# loggerV3_0.net
KiCad netlist of a schematic drawn in EAGLE
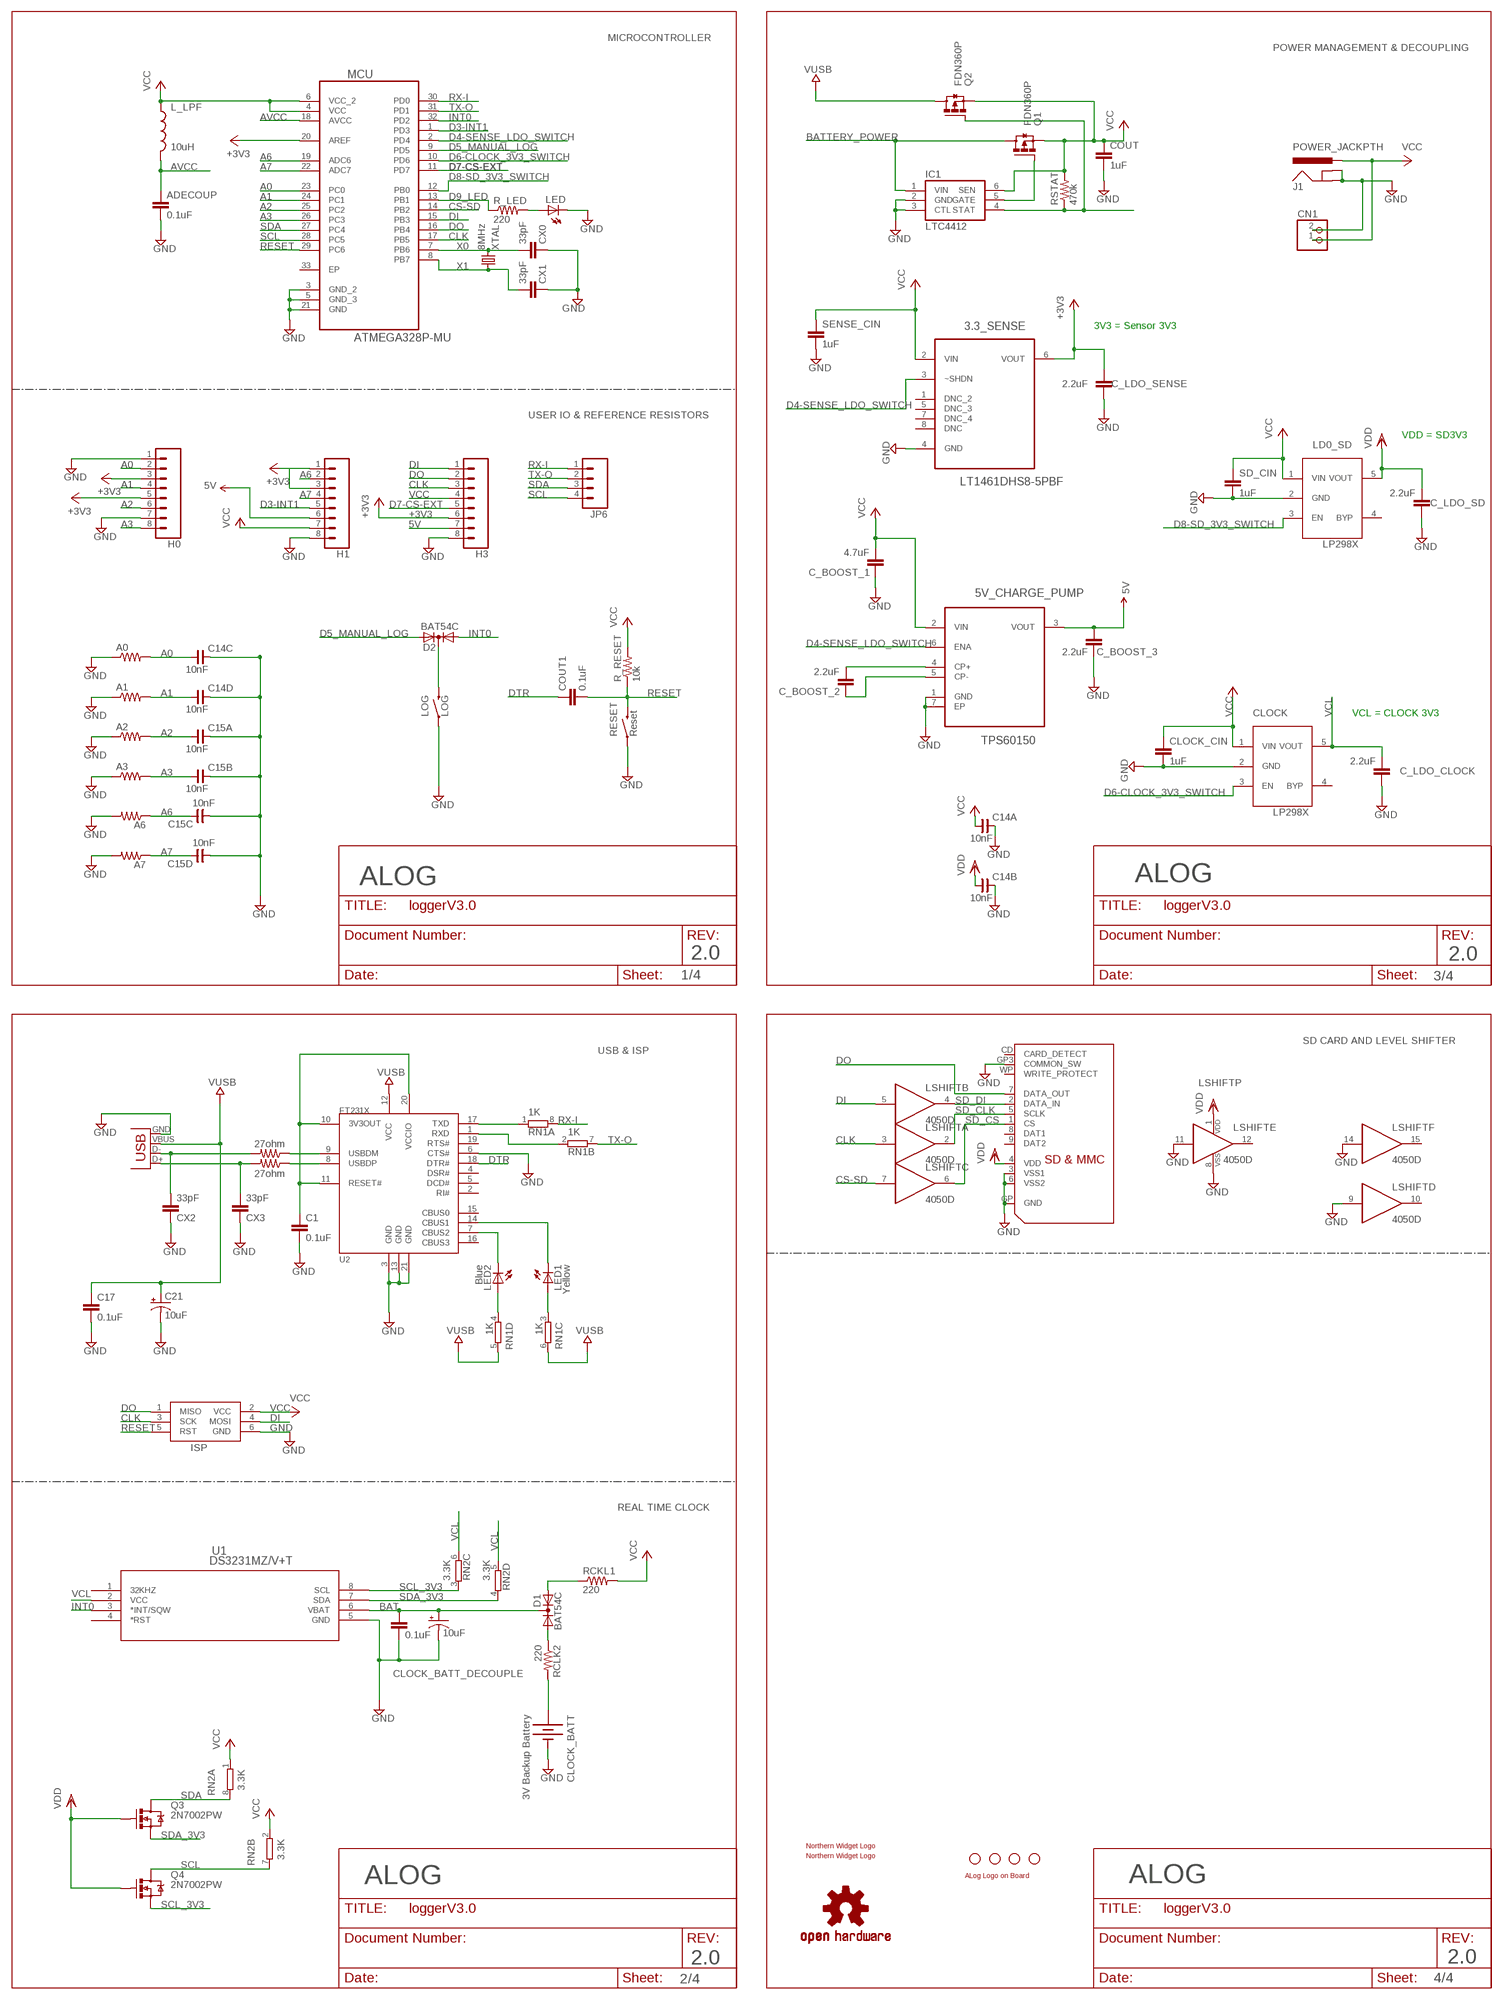
[diagram p0: schematic, sheet 1]

(export (version "E")
  (design (tool "Eeschema 10.0.6"))
  (components
    (comp (ref "3.3_SENSE")
      (value "LT1461DHS8-5PBF")
      (footprint "eagle-import:SOIC127P600X175-8N")
      (fields (field (name "MPN") "LT1461DHS8-5#PBF"))
      (libsource (lib "eagle-import") (part "LT1461DHS8-5PBF"))
    )
    (comp (ref "5V_CHARGE_PUMP")
      (value "TPS60150")
      (footprint "eagle-import:SON65P200X200X80-7N")
      (fields (field (name "MPN") "TPS60150DRVR"))
      (libsource (lib "eagle-import") (part "TPS60150DRVR"))
    )
    (comp (ref "A0")
      (value "R-US_0207/10")
      (footprint "eagle-import:0207_10")
      (libsource (lib "eagle-import") (part "resistor_R-US_0207/10"))
    )
    (comp (ref "A1")
      (value "R-US_0207/10")
      (footprint "eagle-import:0207_10")
      (libsource (lib "eagle-import") (part "resistor_R-US_0207/10"))
    )
    (comp (ref "A2")
      (value "R-US_0207/10")
      (footprint "eagle-import:0207_10")
      (libsource (lib "eagle-import") (part "resistor_R-US_0207/10"))
    )
    (comp (ref "A3")
      (value "R-US_0207/10")
      (footprint "eagle-import:0207_10")
      (libsource (lib "eagle-import") (part "resistor_R-US_0207/10"))
    )
    (comp (ref "A6")
      (value "R-US_0207/10")
      (footprint "eagle-import:0207_10")
      (libsource (lib "eagle-import") (part "resistor_R-US_0207/10"))
    )
    (comp (ref "A7")
      (value "R-US_0207/10")
      (footprint "eagle-import:0207_10")
      (libsource (lib "eagle-import") (part "resistor_R-US_0207/10"))
    )
    (comp (ref "ADECOUP")
      (value "0.1uF")
      (footprint "eagle-import:C0603")
      (libsource (lib "eagle-import") (part "resistor_C-EUC0603"))
    )
    (comp (ref "C1")
      (value "0.1uF")
      (footprint "eagle-import:C0603")
      (libsource (lib "eagle-import") (part "resistor_C-EUC0603"))
    )
    (comp (ref "C14")
      (value "10nF")
      (footprint "eagle-import:CECJ-1206")
      (libsource (lib "eagle-import") (part "CCA_ECJ-1206"))
    )
    (comp (ref "C15")
      (value "10nF")
      (footprint "eagle-import:CECJ-1206")
      (libsource (lib "eagle-import") (part "CCA_ECJ-1206"))
    )
    (comp (ref "C17")
      (value "0.1uF")
      (footprint "eagle-import:C0603")
      (libsource (lib "eagle-import") (part "resistor_C-EUC0603"))
    )
    (comp (ref "C21")
      (value "10uF")
      (footprint "eagle-import:EIA3216")
      (libsource (lib "eagle-import") (part "CAP_POL1206"))
    )
    (comp (ref "CLOCK")
      (value "LP2985")
      (footprint "eagle-import:SOT23-5L")
      (libsource (lib "eagle-import") (part "LP298XS"))
    )
    (comp (ref "CLOCK_BATT")
      (value "3V Backup Battery")
      (footprint "eagle-import:BATTCON_12MM_PTH")
      (libsource (lib "eagle-import") (part "BATTERY12PTH"))
    )
    (comp (ref "CLOCK_BATT_DECOUP")
      (value "0.1uF")
      (footprint "eagle-import:C0603")
      (libsource (lib "eagle-import") (part "C-EUC0603"))
    )
    (comp (ref "CLOCK_BATT_DECOUPLE")
      (value "10uF")
      (footprint "eagle-import:EIA3216")
      (libsource (lib "eagle-import") (part "CAP_POL1206"))
    )
    (comp (ref "CLOCK_CIN")
      (value "1uF")
      (footprint "eagle-import:C0603")
      (libsource (lib "eagle-import") (part "C-EUC0603"))
    )
    (comp (ref "CN1")
      (value "JST_2PIN-THM")
      (footprint "eagle-import:JST-PH-2-THM")
      (libsource (lib "eagle-import") (part "JST_2PIN-THM"))
    )
    (comp (ref "COUT")
      (value "1uF")
      (footprint "eagle-import:C0603")
      (libsource (lib "eagle-import") (part "C-EUC0603"))
    )
    (comp (ref "COUT1")
      (value "0.1uF")
      (footprint "eagle-import:C0603")
      (libsource (lib "eagle-import") (part "C-EUC0603"))
    )
    (comp (ref "CX0")
      (value "33pF")
      (footprint "eagle-import:C0603")
      (libsource (lib "eagle-import") (part "resistor_C-EUC0603"))
    )
    (comp (ref "CX1")
      (value "33pF")
      (footprint "eagle-import:C0603")
      (libsource (lib "eagle-import") (part "resistor_C-EUC0603"))
    )
    (comp (ref "CX2")
      (value "33pF")
      (footprint "eagle-import:C0603")
      (libsource (lib "eagle-import") (part "resistor_C-EUC0603"))
    )
    (comp (ref "CX3")
      (value "33pF")
      (footprint "eagle-import:C0603")
      (libsource (lib "eagle-import") (part "resistor_C-EUC0603"))
    )
    (comp (ref "C_BOOST_1")
      (value "4.7uF")
      (footprint "eagle-import:C0603")
      (libsource (lib "eagle-import") (part "resistor_C-EUC0603"))
    )
    (comp (ref "C_BOOST_2")
      (value "2.2uF")
      (footprint "eagle-import:C0603")
      (libsource (lib "eagle-import") (part "resistor_C-EUC0603"))
    )
    (comp (ref "C_BOOST_3")
      (value "2.2uF")
      (footprint "eagle-import:C0603")
      (libsource (lib "eagle-import") (part "resistor_C-EUC0603"))
    )
    (comp (ref "C_LDO_CLOCK")
      (value "2.2uF")
      (footprint "eagle-import:C0603")
      (libsource (lib "eagle-import") (part "resistor_C-EUC0603"))
    )
    (comp (ref "C_LDO_SD")
      (value "2.2uF")
      (footprint "eagle-import:C0603")
      (libsource (lib "eagle-import") (part "resistor_C-EUC0603"))
    )
    (comp (ref "C_LDO_SENSE")
      (value "2.2uF")
      (footprint "eagle-import:C0603")
      (libsource (lib "eagle-import") (part "resistor_C-EUC0603"))
    )
    (comp (ref "D+")
      (value "27ohm")
      (footprint "eagle-import:R0603")
      (libsource (lib "eagle-import") (part "R-US_R0603"))
    )
    (comp (ref "D-")
      (value "27ohm")
      (footprint "eagle-import:R0603")
      (libsource (lib "eagle-import") (part "R-US_R0603"))
    )
    (comp (ref "D1")
      (value "BAT54C")
      (footprint "eagle-import:SOT23C")
      (libsource (lib "eagle-import") (part "DIODE_AC-CA_"))
    )
    (comp (ref "D2")
      (value "BAT54C")
      (footprint "eagle-import:SOT23C")
      (libsource (lib "eagle-import") (part "DIODE_AC-CA_"))
    )
    (comp (ref "H0")
      (value "M083.5MM-8")
      (footprint "eagle-import:SCREWTERMINAL-3.5MM-8")
      (libsource (lib "eagle-import") (part "M083.5MM-8"))
    )
    (comp (ref "H1")
      (value "M083.5MM-8")
      (footprint "eagle-import:SCREWTERMINAL-3.5MM-8")
      (libsource (lib "eagle-import") (part "M083.5MM-8"))
    )
    (comp (ref "H3")
      (value "M083.5MM-8")
      (footprint "eagle-import:SCREWTERMINAL-3.5MM-8")
      (libsource (lib "eagle-import") (part "M083.5MM-8"))
    )
    (comp (ref "IC1")
      (value "LTC4412")
      (footprint "eagle-import:TSOT23-6")
      (libsource (lib "eagle-import") (part "LTC4412S6E"))
    )
    (comp (ref "ISP")
      (value "AVRISP-6")
      (footprint "eagle-import:AVRISP")
      (libsource (lib "eagle-import") (part "AVRISP-6"))
    )
    (comp (ref "J1")
      (value "POWER_JACKPTH")
      (footprint "eagle-import:POWER_JACK_PTH")
      (libsource (lib "eagle-import") (part "POWER_JACKPTH"))
    )
    (comp (ref "JP1")
      (value "STAND-OFF")
      (footprint "eagle-import:STAND-OFF")
      (libsource (lib "eagle-import") (part "STAND-OFF"))
    )
    (comp (ref "JP2")
      (value "STAND-OFF")
      (footprint "eagle-import:STAND-OFF")
      (libsource (lib "eagle-import") (part "STAND-OFF"))
    )
    (comp (ref "JP3")
      (value "STAND-OFF")
      (footprint "eagle-import:STAND-OFF")
      (libsource (lib "eagle-import") (part "STAND-OFF"))
    )
    (comp (ref "JP4")
      (value "STAND-OFF")
      (footprint "eagle-import:STAND-OFF")
      (libsource (lib "eagle-import") (part "STAND-OFF"))
    )
    (comp (ref "JP5")
      (value "USB-B")
      (footprint "eagle-import:USB-B-PTH")
      (libsource (lib "eagle-import") (part "USBPTH"))
    )
    (comp (ref "JP6")
      (value "M04SCREW")
      (footprint "eagle-import:SCREWTERMINAL-3.5MM-4")
      (libsource (lib "eagle-import") (part "M04SCREW"))
    )
    (comp (ref "LD0_SD")
      (value "LP2985")
      (footprint "eagle-import:SOT23-5L")
      (libsource (lib "eagle-import") (part "LP298XS"))
    )
    (comp (ref "LED")
      (value "LED3MM")
      (footprint "eagle-import:LED3MM")
      (libsource (lib "eagle-import") (part "LED3MM"))
    )
    (comp (ref "LED1")
      (value "Yellow")
      (footprint "eagle-import:LED-0603")
      (libsource (lib "eagle-import") (part "SparkFun-LED_LED0603"))
    )
    (comp (ref "LED2")
      (value "Blue")
      (footprint "eagle-import:LED-0603")
      (libsource (lib "eagle-import") (part "SparkFun-LED_LED0603"))
    )
    (comp (ref "LOG")
      (value "LOG")
      (footprint "eagle-import:TACTILE-PTH")
      (libsource (lib "eagle-import") (part "SWITCH-MOMENTARY-2PTH"))
    )
    (comp (ref "LOGO1")
      (value "OSHW-LOGOM")
      (footprint "eagle-import:OSHW-LOGO-M")
      (libsource (lib "eagle-import") (part "OSHW-LOGOM"))
    )
    (comp (ref "LSHIFT")
      (value "4050D")
      (footprint "eagle-import:SO16")
      (libsource (lib "eagle-import") (part "4050D"))
    )
    (comp (ref "L_LPF")
      (value "10uH")
      (footprint "eagle-import:0805")
      (libsource (lib "eagle-import") (part "INDUCTOR0805"))
    )
    (comp (ref "MCU")
      (value "ATMEGA328P-MU")
      (footprint "eagle-import:QFN50P500X500X100-33N")
      (libsource (lib "eagle-import") (part "ATMEGA328P-MU"))
    )
    (comp (ref "Q1")
      (value "FDN360P")
      (footprint "eagle-import:SUPER-SOT3")
      (libsource (lib "eagle-import") (part "FDN360P"))
    )
    (comp (ref "Q2")
      (value "FDN360P")
      (footprint "eagle-import:SUPER-SOT3")
      (libsource (lib "eagle-import") (part "FDN360P"))
    )
    (comp (ref "Q3")
      (value "2N7002PW")
      (footprint "eagle-import:SOT323")
      (libsource (lib "eagle-import") (part "MOSFET-NCHANNELSOT323"))
    )
    (comp (ref "Q4")
      (value "2N7002PW")
      (footprint "eagle-import:SOT323")
      (libsource (lib "eagle-import") (part "MOSFET-NCHANNELSOT323"))
    )
    (comp (ref "RCKL1")
      (value "220")
      (footprint "eagle-import:R0603")
      (libsource (lib "eagle-import") (part "R-US_R0603"))
    )
    (comp (ref "RCLK2")
      (value "220")
      (footprint "eagle-import:R0603")
      (libsource (lib "eagle-import") (part "R-US_R0603"))
    )
    (comp (ref "RESET")
      (value "Reset")
      (footprint "eagle-import:TACTILE-PTH")
      (libsource (lib "eagle-import") (part "SWITCH-MOMENTARY-2PTH"))
    )
    (comp (ref "RN1")
      (value "1K")
      (footprint "eagle-import:0603-ARC")
      (libsource (lib "eagle-import") (part "4R-N0603-ARC"))
    )
    (comp (ref "RN2")
      (value "3.3K")
      (footprint "eagle-import:0603-ARC")
      (libsource (lib "eagle-import") (part "4R-N0603-ARC"))
    )
    (comp (ref "RSTAT")
      (value "470k")
      (footprint "eagle-import:R0603")
      (libsource (lib "eagle-import") (part "R-US_R0603"))
    )
    (comp (ref "R_LED")
      (value "220")
      (footprint "eagle-import:R0603")
      (libsource (lib "eagle-import") (part "resistor_R-US_R0603"))
    )
    (comp (ref "R_RESET")
      (value "10k")
      (footprint "eagle-import:R0603")
      (libsource (lib "eagle-import") (part "R-US_R0603"))
    )
    (comp (ref "SD")
      (value "SDMMC06132")
      (footprint "eagle-import:06132")
      (libsource (lib "eagle-import") (part "SDMMC06132"))
    )
    (comp (ref "SD_CIN")
      (value "1uF")
      (footprint "eagle-import:C0603")
      (libsource (lib "eagle-import") (part "C-EUC0603"))
    )
    (comp (ref "SENSE_CIN")
      (value "1uF")
      (footprint "eagle-import:C0603")
      (libsource (lib "eagle-import") (part "C-EUC0603"))
    )
    (comp (ref "U$1")
      (value "NWLOGO")
      (footprint "eagle-import:NWLOGO")
      (libsource (lib "eagle-import") (part "NWLOGO"))
    )
    (comp (ref "U$2")
      (value "ALOG_LOGO_V1_5.5MM")
      (footprint "eagle-import:ALOG_LOGO_V1_SMALL")
      (libsource (lib "eagle-import") (part "ALOG_LOGO_V1_5.5MM"))
    )
    (comp (ref "U$3")
      (value "NWLOGO_MED")
      (footprint "eagle-import:NWLOGO_MED")
      (libsource (lib "eagle-import") (part "NWLOGO_MED"))
    )
    (comp (ref "U1")
      (value "DS3231MZ/V+T")
      (footprint "eagle-import:21-0041B_8")
      (libsource (lib "eagle-import") (part "DS3231MZ/V+T"))
    )
    (comp (ref "U2")
      (value "FT231X-Q")
      (footprint "eagle-import:QFN20")
      (libsource (lib "eagle-import") (part "FT231X-Q"))
    )
    (comp (ref "XTAL")
      (value "8MHz")
      (footprint "eagle-import:HC49U-V")
      (libsource (lib "eagle-import") (part "CRYSTALHC49UV"))
    )
  )
  (nets
    (net (code "1") (name "+3V3") (class "Default")
      (node (ref "3.3_SENSE") (pin "6") (pinfunction "VOUT_6") (pintype "output"))
      (node (ref "C_LDO_SENSE") (pin "2") (pinfunction "2_2") (pintype "passive"))
      (node (ref "H0") (pin "3") (pinfunction "3_3") (pintype "passive"))
      (node (ref "H0") (pin "5") (pinfunction "5_5") (pintype "passive"))
      (node (ref "H1") (pin "1") (pinfunction "1_1") (pintype "passive"))
      (node (ref "H1") (pin "3") (pinfunction "3_3") (pintype "passive"))
      (node (ref "H3") (pin "6") (pinfunction "6_6") (pintype "passive"))
      (node (ref "MCU") (pin "20") (pinfunction "AREF_20") (pintype "input"))
    )
    (net (code "2") (name "/A0") (class "Default")
      (node (ref "A0") (pin "2") (pinfunction "2_2") (pintype "passive"))
      (node (ref "C14") (pin "C1") (pinfunction "1_C1") (pintype "passive"))
      (node (ref "H0") (pin "2") (pinfunction "2_2") (pintype "passive"))
      (node (ref "MCU") (pin "23") (pinfunction "PC0_23") (pintype "bidirectional"))
    )
    (net (code "3") (name "/A1") (class "Default")
      (node (ref "A1") (pin "2") (pinfunction "2_2") (pintype "passive"))
      (node (ref "C14") (pin "D1") (pinfunction "1_D1") (pintype "passive"))
      (node (ref "H0") (pin "4") (pinfunction "4_4") (pintype "passive"))
      (node (ref "MCU") (pin "24") (pinfunction "PC1_24") (pintype "bidirectional"))
    )
    (net (code "4") (name "/A2") (class "Default")
      (node (ref "A2") (pin "2") (pinfunction "2_2") (pintype "passive"))
      (node (ref "C15") (pin "A1") (pinfunction "1_A1") (pintype "passive"))
      (node (ref "H0") (pin "6") (pinfunction "6_6") (pintype "passive"))
      (node (ref "MCU") (pin "25") (pinfunction "PC2_25") (pintype "bidirectional"))
    )
    (net (code "5") (name "/A3") (class "Default")
      (node (ref "A3") (pin "2") (pinfunction "2_2") (pintype "passive"))
      (node (ref "C15") (pin "B1") (pinfunction "1_B1") (pintype "passive"))
      (node (ref "H0") (pin "8") (pinfunction "8_8") (pintype "passive"))
      (node (ref "MCU") (pin "26") (pinfunction "PC3_26") (pintype "bidirectional"))
    )
    (net (code "6") (name "/A6") (class "Default")
      (node (ref "A6") (pin "1") (pinfunction "1_1") (pintype "passive"))
      (node (ref "C15") (pin "C2") (pinfunction "2_C2") (pintype "passive"))
      (node (ref "H1") (pin "2") (pinfunction "2_2") (pintype "passive"))
      (node (ref "MCU") (pin "19") (pinfunction "ADC6_19") (pintype "input"))
    )
    (net (code "7") (name "/A7") (class "Default")
      (node (ref "A7") (pin "1") (pinfunction "1_1") (pintype "passive"))
      (node (ref "C15") (pin "D2") (pinfunction "2_D2") (pintype "passive"))
      (node (ref "H1") (pin "4") (pinfunction "4_4") (pintype "passive"))
      (node (ref "MCU") (pin "22") (pinfunction "ADC7_22") (pintype "input"))
    )
    (net (code "8") (name "/AVCC") (class "Default")
      (node (ref "ADECOUP") (pin "1") (pinfunction "1_1") (pintype "passive"))
      (node (ref "L_LPF") (pin "2") (pinfunction "2_2") (pintype "passive"))
      (node (ref "MCU") (pin "18") (pinfunction "AVCC_18") (pintype "power_in"))
    )
    (net (code "9") (name "/BAT") (class "Default")
      (node (ref "CLOCK_BATT_DECOUP") (pin "1") (pinfunction "1_1") (pintype "passive"))
      (node (ref "CLOCK_BATT_DECOUPLE") (pin "A") (pinfunction "+_A") (pintype "passive"))
      (node (ref "D1") (pin "3") (pinfunction "K_3") (pintype "passive"))
      (node (ref "U1") (pin "6") (pinfunction "VBAT_6") (pintype "power_in"))
    )
    (net (code "10") (name "/BATTERY_POWER") (class "Default")
      (node (ref "IC1") (pin "1") (pinfunction "VIN_1") (pintype "input"))
      (node (ref "Q1") (pin "3") (pinfunction "D_3") (pintype "passive"))
    )
    (net (code "11") (name "/CLK") (class "Default")
      (node (ref "H3") (pin "3") (pinfunction "3_3") (pintype "passive"))
      (node (ref "ISP") (pin "3") (pinfunction "SCK_3") (pintype "output"))
      (node (ref "LSHIFT") (pin "3") (pinfunction "I_3") (pintype "input"))
      (node (ref "MCU") (pin "17") (pinfunction "PB5_17") (pintype "bidirectional"))
    )
    (net (code "12") (name "/CS-SD") (class "Default")
      (node (ref "LSHIFT") (pin "7") (pinfunction "I_7") (pintype "input"))
      (node (ref "MCU") (pin "14") (pinfunction "PB2_14") (pintype "bidirectional"))
    )
    (net (code "13") (name "/D3-INT1") (class "Default")
      (node (ref "H1") (pin "5") (pinfunction "5_5") (pintype "passive"))
      (node (ref "MCU") (pin "1") (pinfunction "PD3_1") (pintype "bidirectional"))
    )
    (net (code "14") (name "/D4-SENSE_LDO_SWITCH") (class "Default")
      (node (ref "3.3_SENSE") (pin "3") (pinfunction "~{SHDN}_3") (pintype "input"))
      (node (ref "5V_CHARGE_PUMP") (pin "6") (pinfunction "ENA_6") (pintype "input"))
      (node (ref "MCU") (pin "2") (pinfunction "PD4_2") (pintype "bidirectional"))
    )
    (net (code "15") (name "/D5_MANUAL_LOG") (class "Default")
      (node (ref "D2") (pin "2") (pinfunction "A2_2") (pintype "passive"))
      (node (ref "MCU") (pin "9") (pinfunction "PD5_9") (pintype "bidirectional"))
    )
    (net (code "16") (name "/D6-CLOCK_3V3_SWITCH") (class "Default")
      (node (ref "CLOCK") (pin "3") (pinfunction "EN_3") (pintype "bidirectional"))
      (node (ref "MCU") (pin "10") (pinfunction "PD6_10") (pintype "bidirectional"))
    )
    (net (code "17") (name "/D7-CS-EXT") (class "Default")
      (node (ref "H3") (pin "5") (pinfunction "5_5") (pintype "passive"))
      (node (ref "MCU") (pin "11") (pinfunction "PD7_11") (pintype "bidirectional"))
    )
    (net (code "18") (name "/D8-SD_3V3_SWITCH") (class "Default")
      (node (ref "LD0_SD") (pin "3") (pinfunction "EN_3") (pintype "bidirectional"))
      (node (ref "MCU") (pin "12") (pinfunction "PB0_12") (pintype "bidirectional"))
    )
    (net (code "19") (name "/D9_LED") (class "Default")
      (node (ref "MCU") (pin "13") (pinfunction "PB1_13") (pintype "bidirectional"))
      (node (ref "R_LED") (pin "1") (pinfunction "1_1") (pintype "passive"))
    )
    (net (code "20") (name "/DI") (class "Default")
      (node (ref "H3") (pin "1") (pinfunction "1_1") (pintype "passive"))
      (node (ref "ISP") (pin "4") (pinfunction "MOSI_4") (pintype "output"))
      (node (ref "LSHIFT") (pin "5") (pinfunction "I_5") (pintype "input"))
      (node (ref "MCU") (pin "15") (pinfunction "PB3_15") (pintype "bidirectional"))
    )
    (net (code "21") (name "/DO") (class "Default")
      (node (ref "H3") (pin "2") (pinfunction "2_2") (pintype "passive"))
      (node (ref "ISP") (pin "1") (pinfunction "MISO_1") (pintype "input"))
      (node (ref "MCU") (pin "16") (pinfunction "PB4_16") (pintype "bidirectional"))
      (node (ref "SD") (pin "7") (pinfunction "DATA_OUT_7") (pintype "output"))
    )
    (net (code "22") (name "/DTR") (class "Default")
      (node (ref "COUT1") (pin "1") (pinfunction "1_1") (pintype "passive"))
      (node (ref "U2") (pin "18") (pinfunction "DTR#_18") (pintype "bidirectional"))
    )
    (net (code "23") (name "/INT0") (class "Default")
      (node (ref "D2") (pin "1") (pinfunction "A1_1") (pintype "passive"))
      (node (ref "MCU") (pin "32") (pinfunction "PD2_32") (pintype "bidirectional"))
      (node (ref "U1") (pin "3") (pinfunction "*INT/SQW_3") (pintype "passive"))
    )
    (net (code "24") (name "/RESET") (class "Default")
      (node (ref "COUT1") (pin "2") (pinfunction "2_2") (pintype "passive"))
      (node (ref "ISP") (pin "5") (pinfunction "RST_5") (pintype "output"))
      (node (ref "MCU") (pin "29") (pinfunction "PC6_29") (pintype "bidirectional"))
      (node (ref "RESET") (pin "3") (pinfunction "2_3") (pintype "passive"))
      (node (ref "R_RESET") (pin "1") (pinfunction "1_1") (pintype "passive"))
    )
    (net (code "25") (name "/RX-I") (class "Default")
      (node (ref "JP6") (pin "1") (pinfunction "1_1") (pintype "passive"))
      (node (ref "MCU") (pin "30") (pinfunction "PD0_30") (pintype "bidirectional"))
      (node (ref "RN1") (pin "8") (pinfunction "2_8") (pintype "passive"))
    )
    (net (code "26") (name "/SCL") (class "Default")
      (node (ref "JP6") (pin "4") (pinfunction "4_4") (pintype "passive"))
      (node (ref "MCU") (pin "28") (pinfunction "PC5_28") (pintype "bidirectional"))
      (node (ref "Q4") (pin "3") (pinfunction "D_3") (pintype "passive"))
      (node (ref "RN2") (pin "7") (pinfunction "2_7") (pintype "passive"))
    )
    (net (code "27") (name "/SCL_3V3") (class "Default")
      (node (ref "Q4") (pin "2") (pinfunction "S_2") (pintype "passive"))
      (node (ref "RN2") (pin "3") (pinfunction "1_3") (pintype "passive"))
      (node (ref "U1") (pin "8") (pinfunction "SCL_8") (pintype "passive"))
    )
    (net (code "28") (name "/SDA") (class "Default")
      (node (ref "JP6") (pin "3") (pinfunction "3_3") (pintype "passive"))
      (node (ref "MCU") (pin "27") (pinfunction "PC4_27") (pintype "bidirectional"))
      (node (ref "Q3") (pin "3") (pinfunction "D_3") (pintype "passive"))
      (node (ref "RN2") (pin "8") (pinfunction "2_8") (pintype "passive"))
    )
    (net (code "29") (name "/SDA_3V3") (class "Default")
      (node (ref "Q3") (pin "2") (pinfunction "S_2") (pintype "passive"))
      (node (ref "RN2") (pin "4") (pinfunction "1_4") (pintype "passive"))
      (node (ref "U1") (pin "7") (pinfunction "SDA_7") (pintype "passive"))
    )
    (net (code "30") (name "/SD_CLK") (class "Default")
      (node (ref "LSHIFT") (pin "2") (pinfunction "O_2") (pintype "output"))
      (node (ref "SD") (pin "5") (pinfunction "SCLK_5") (pintype "input"))
    )
    (net (code "31") (name "/SD_CS") (class "Default")
      (node (ref "LSHIFT") (pin "6") (pinfunction "O_6") (pintype "output"))
      (node (ref "SD") (pin "1") (pinfunction "CS_1") (pintype "input"))
    )
    (net (code "32") (name "/SD_DI") (class "Default")
      (node (ref "LSHIFT") (pin "4") (pinfunction "O_4") (pintype "output"))
      (node (ref "SD") (pin "2") (pinfunction "DATA_IN_2") (pintype "input"))
    )
    (net (code "33") (name "/TX-O") (class "Default")
      (node (ref "JP6") (pin "2") (pinfunction "2_2") (pintype "passive"))
      (node (ref "MCU") (pin "31") (pinfunction "PD1_31") (pintype "bidirectional"))
      (node (ref "RN1") (pin "7") (pinfunction "2_7") (pintype "passive"))
    )
    (net (code "34") (name "/VCL") (class "Default")
      (node (ref "CLOCK") (pin "5") (pinfunction "VOUT_5") (pintype "bidirectional"))
      (node (ref "C_LDO_CLOCK") (pin "2") (pinfunction "2_2") (pintype "passive"))
      (node (ref "RN2") (pin "5") (pinfunction "2_5") (pintype "passive"))
      (node (ref "RN2") (pin "6") (pinfunction "2_6") (pintype "passive"))
      (node (ref "U1") (pin "2") (pinfunction "VCC_2") (pintype "power_in"))
    )
    (net (code "35") (name "/X0") (class "Default")
      (node (ref "CX0") (pin "2") (pinfunction "2_2") (pintype "passive"))
      (node (ref "MCU") (pin "7") (pinfunction "PB6_7") (pintype "bidirectional"))
      (node (ref "XTAL") (pin "2") (pinfunction "2_2") (pintype "passive"))
    )
    (net (code "36") (name "/X1") (class "Default")
      (node (ref "CX1") (pin "2") (pinfunction "2_2") (pintype "passive"))
      (node (ref "MCU") (pin "8") (pinfunction "PB7_8") (pintype "bidirectional"))
      (node (ref "XTAL") (pin "1") (pinfunction "1_1") (pintype "passive"))
    )
    (net (code "37") (name "5V") (class "Default")
      (node (ref "5V_CHARGE_PUMP") (pin "3") (pinfunction "VOUT_3") (pintype "output"))
      (node (ref "C_BOOST_3") (pin "2") (pinfunction "2_2") (pintype "passive"))
      (node (ref "H1") (pin "6") (pinfunction "6_6") (pintype "passive"))
      (node (ref "H3") (pin "7") (pinfunction "7_7") (pintype "passive"))
    )
    (net (code "38") (name "GND") (class "Default")
      (node (ref "3.3_SENSE") (pin "4") (pinfunction "GND_4") (pintype "passive"))
      (node (ref "5V_CHARGE_PUMP") (pin "1") (pinfunction "GND_1") (pintype "passive"))
      (node (ref "5V_CHARGE_PUMP") (pin "7") (pinfunction "EP_7") (pintype "passive"))
      (node (ref "A0") (pin "1") (pinfunction "1_1") (pintype "passive"))
      (node (ref "A1") (pin "1") (pinfunction "1_1") (pintype "passive"))
      (node (ref "A2") (pin "1") (pinfunction "1_1") (pintype "passive"))
      (node (ref "A3") (pin "1") (pinfunction "1_1") (pintype "passive"))
      (node (ref "A6") (pin "2") (pinfunction "2_2") (pintype "passive"))
      (node (ref "A7") (pin "2") (pinfunction "2_2") (pintype "passive"))
      (node (ref "ADECOUP") (pin "2") (pinfunction "2_2") (pintype "passive"))
      (node (ref "C1") (pin "2") (pinfunction "2_2") (pintype "passive"))
      (node (ref "C14") (pin "A2") (pinfunction "2_A2") (pintype "passive"))
      (node (ref "C14") (pin "B2") (pinfunction "2_B2") (pintype "passive"))
      (node (ref "C14") (pin "C2") (pinfunction "2_C2") (pintype "passive"))
      (node (ref "C14") (pin "D2") (pinfunction "2_D2") (pintype "passive"))
      (node (ref "C15") (pin "A2") (pinfunction "2_A2") (pintype "passive"))
      (node (ref "C15") (pin "B2") (pinfunction "2_B2") (pintype "passive"))
      (node (ref "C15") (pin "C1") (pinfunction "1_C1") (pintype "passive"))
      (node (ref "C15") (pin "D1") (pinfunction "1_D1") (pintype "passive"))
      (node (ref "C17") (pin "2") (pinfunction "2_2") (pintype "passive"))
      (node (ref "C21") (pin "C") (pinfunction "-_C") (pintype "passive"))
      (node (ref "CLOCK") (pin "2") (pinfunction "GND_2") (pintype "bidirectional"))
      (node (ref "CLOCK_BATT") (pin "GND") (pinfunction "-_GND") (pintype "power_in"))
      (node (ref "CLOCK_BATT_DECOUP") (pin "2") (pinfunction "2_2") (pintype "passive"))
      (node (ref "CLOCK_BATT_DECOUPLE") (pin "C") (pinfunction "-_C") (pintype "passive"))
      (node (ref "CLOCK_CIN") (pin "2") (pinfunction "2_2") (pintype "passive"))
      (node (ref "CN1") (pin "2") (pinfunction "1_2") (pintype "passive"))
      (node (ref "COUT") (pin "2") (pinfunction "2_2") (pintype "passive"))
      (node (ref "CX0") (pin "1") (pinfunction "1_1") (pintype "passive"))
      (node (ref "CX1") (pin "1") (pinfunction "1_1") (pintype "passive"))
      (node (ref "CX2") (pin "1") (pinfunction "1_1") (pintype "passive"))
      (node (ref "CX3") (pin "1") (pinfunction "1_1") (pintype "passive"))
      (node (ref "C_BOOST_1") (pin "1") (pinfunction "1_1") (pintype "passive"))
      (node (ref "C_BOOST_3") (pin "1") (pinfunction "1_1") (pintype "passive"))
      (node (ref "C_LDO_CLOCK") (pin "1") (pinfunction "1_1") (pintype "passive"))
      (node (ref "C_LDO_SD") (pin "1") (pinfunction "1_1") (pintype "passive"))
      (node (ref "C_LDO_SENSE") (pin "1") (pinfunction "1_1") (pintype "passive"))
      (node (ref "H0") (pin "1") (pinfunction "1_1") (pintype "passive"))
      (node (ref "H0") (pin "7") (pinfunction "7_7") (pintype "passive"))
      (node (ref "H1") (pin "8") (pinfunction "8_8") (pintype "passive"))
      (node (ref "H3") (pin "8") (pinfunction "8_8") (pintype "passive"))
      (node (ref "IC1") (pin "2") (pinfunction "GND_2") (pintype "passive"))
      (node (ref "IC1") (pin "3") (pinfunction "CTL_3") (pintype "input"))
      (node (ref "ISP") (pin "6") (pinfunction "GND_6") (pintype "power_in"))
      (node (ref "J1") (pin "GND") (pinfunction "GND_GND") (pintype "bidirectional"))
      (node (ref "J1") (pin "GNDBREAK") (pinfunction "GNDBREAK_GNDBREAK") (pintype "bidirectional"))
      (node (ref "JP5") (pin "GND") (pinfunction "GND_GND") (pintype "bidirectional"))
      (node (ref "LD0_SD") (pin "2") (pinfunction "GND_2") (pintype "bidirectional"))
      (node (ref "LED") (pin "K") (pinfunction "C_K") (pintype "passive"))
      (node (ref "LOG") (pin "1") (pinfunction "1_1") (pintype "passive"))
      (node (ref "LSHIFT") (pin "11") (pinfunction "I_11") (pintype "input"))
      (node (ref "LSHIFT") (pin "14") (pinfunction "I_14") (pintype "input"))
      (node (ref "LSHIFT") (pin "8") (pinfunction "VSS_8") (pintype "power_in"))
      (node (ref "LSHIFT") (pin "9") (pinfunction "I_9") (pintype "input"))
      (node (ref "MCU") (pin "21") (pinfunction "GND_21") (pintype "passive"))
      (node (ref "MCU") (pin "3") (pinfunction "GND_2_3") (pintype "passive"))
      (node (ref "MCU") (pin "5") (pinfunction "GND_3_5") (pintype "passive"))
      (node (ref "RESET") (pin "1") (pinfunction "1_1") (pintype "passive"))
      (node (ref "SD") (pin "3") (pinfunction "VSS1_3") (pintype "power_in"))
      (node (ref "SD") (pin "6") (pinfunction "VSS2_6") (pintype "power_in"))
      (node (ref "SD") (pin "GP") (pinfunction "GND_GP") (pintype "power_in"))
      (node (ref "SD") (pin "GP3") (pinfunction "COMMON_SW_GP3") (pintype "passive"))
      (node (ref "SD_CIN") (pin "2") (pinfunction "2_2") (pintype "passive"))
      (node (ref "SENSE_CIN") (pin "2") (pinfunction "2_2") (pintype "passive"))
      (node (ref "U1") (pin "5") (pinfunction "GND_5") (pintype "power_in"))
      (node (ref "U2") (pin "13") (pinfunction "GND_13") (pintype "bidirectional"))
      (node (ref "U2") (pin "21") (pinfunction "GND_21") (pintype "bidirectional"))
      (node (ref "U2") (pin "3") (pinfunction "GND_3") (pintype "bidirectional"))
      (node (ref "U2") (pin "6") (pinfunction "CTS#_6") (pintype "bidirectional"))
    )
    (net (code "39") (name "Net-(5V_CHARGE_PUMP-CP+)") (class "Default")
      (node (ref "5V_CHARGE_PUMP") (pin "4") (pinfunction "CP+_4") (pintype "passive"))
      (node (ref "C_BOOST_2") (pin "2") (pinfunction "2_2") (pintype "passive"))
    )
    (net (code "40") (name "Net-(5V_CHARGE_PUMP-CP-)") (class "Default")
      (node (ref "5V_CHARGE_PUMP") (pin "5") (pinfunction "CP-_5") (pintype "passive"))
      (node (ref "C_BOOST_2") (pin "1") (pinfunction "1_1") (pintype "passive"))
    )
    (net (code "41") (name "Net-(CLOCK_BATT-+)") (class "Default")
      (node (ref "CLOCK_BATT") (pin "VCC@1") (pinfunction "+_VCC@1") (pintype "power_in"))
      (node (ref "RCLK2") (pin "2") (pinfunction "2_2") (pintype "passive"))
    )
    (net (code "42") (name "Net-(CX2-Pad2)") (class "Default")
      (node (ref "CX2") (pin "2") (pinfunction "2_2") (pintype "passive"))
      (node (ref "D-") (pin "2") (pinfunction "2_2") (pintype "passive"))
      (node (ref "JP5") (pin "D-") (pinfunction "D-_D-") (pintype "bidirectional"))
    )
    (net (code "43") (name "Net-(CX3-Pad2)") (class "Default")
      (node (ref "CX3") (pin "2") (pinfunction "2_2") (pintype "passive"))
      (node (ref "D+") (pin "2") (pinfunction "2_2") (pintype "passive"))
      (node (ref "JP5") (pin "D+") (pinfunction "D+_D+") (pintype "bidirectional"))
    )
    (net (code "44") (name "Net-(D1-A1)") (class "Default")
      (node (ref "D1") (pin "1") (pinfunction "A1_1") (pintype "passive"))
      (node (ref "RCLK2") (pin "1") (pinfunction "1_1") (pintype "passive"))
    )
    (net (code "45") (name "Net-(D1-A2)") (class "Default")
      (node (ref "D1") (pin "2") (pinfunction "A2_2") (pintype "passive"))
      (node (ref "RCKL1") (pin "1") (pinfunction "1_1") (pintype "passive"))
    )
    (net (code "46") (name "Net-(D2-K)") (class "Default")
      (node (ref "D2") (pin "3") (pinfunction "K_3") (pintype "passive"))
      (node (ref "LOG") (pin "3") (pinfunction "2_3") (pintype "passive"))
    )
    (net (code "47") (name "Net-(IC1-GATE)") (class "Default")
      (node (ref "IC1") (pin "5") (pinfunction "GATE_5") (pintype "output"))
      (node (ref "Q1") (pin "1") (pinfunction "G_1") (pintype "passive"))
    )
    (net (code "48") (name "Net-(IC1-STAT)") (class "Default")
      (node (ref "IC1") (pin "4") (pinfunction "STAT_4") (pintype "open_collector"))
      (node (ref "Q2") (pin "1") (pinfunction "G_1") (pintype "passive"))
      (node (ref "RSTAT") (pin "1") (pinfunction "1_1") (pintype "passive"))
    )
    (net (code "49") (name "Net-(LED-PadA)") (class "Default")
      (node (ref "LED") (pin "A") (pinfunction "A_A") (pintype "passive"))
      (node (ref "R_LED") (pin "2") (pinfunction "2_2") (pintype "passive"))
    )
    (net (code "50") (name "Net-(RN1B-1)") (class "Default")
      (node (ref "RN1") (pin "2") (pinfunction "1_2") (pintype "passive"))
      (node (ref "U2") (pin "1") (pinfunction "RXD_1") (pintype "bidirectional"))
    )
    (net (code "51") (name "Net-(RN1C-1)") (class "Default")
      (node (ref "LED1") (pin "A") (pinfunction "A_A") (pintype "passive"))
      (node (ref "RN1") (pin "3") (pinfunction "1_3") (pintype "passive"))
    )
    (net (code "52") (name "Net-(RN1D-1)") (class "Default")
      (node (ref "LED2") (pin "A") (pinfunction "A_A") (pintype "passive"))
      (node (ref "RN1") (pin "4") (pinfunction "1_4") (pintype "passive"))
    )
    (net (code "53") (name "Net-(U2-3V3OUT)") (class "Default")
      (node (ref "C1") (pin "1") (pinfunction "1_1") (pintype "passive"))
      (node (ref "U2") (pin "10") (pinfunction "3V3OUT_10") (pintype "bidirectional"))
      (node (ref "U2") (pin "11") (pinfunction "RESET#_11") (pintype "bidirectional"))
      (node (ref "U2") (pin "20") (pinfunction "VCCIO_20") (pintype "bidirectional"))
    )
    (net (code "54") (name "Net-(U2-CBUS1)") (class "Default")
      (node (ref "LED1") (pin "C") (pinfunction "C_C") (pintype "passive"))
      (node (ref "U2") (pin "14") (pinfunction "CBUS1_14") (pintype "bidirectional"))
    )
    (net (code "55") (name "Net-(U2-CBUS2)") (class "Default")
      (node (ref "LED2") (pin "C") (pinfunction "C_C") (pintype "passive"))
      (node (ref "U2") (pin "7") (pinfunction "CBUS2_7") (pintype "bidirectional"))
    )
    (net (code "56") (name "Net-(U2-TXD)") (class "Default")
      (node (ref "RN1") (pin "1") (pinfunction "1_1") (pintype "passive"))
      (node (ref "U2") (pin "17") (pinfunction "TXD_17") (pintype "bidirectional"))
    )
    (net (code "57") (name "Net-(U2-USBDM)") (class "Default")
      (node (ref "D-") (pin "1") (pinfunction "1_1") (pintype "passive"))
      (node (ref "U2") (pin "9") (pinfunction "USBDM_9") (pintype "bidirectional"))
    )
    (net (code "58") (name "Net-(U2-USBDP)") (class "Default")
      (node (ref "D+") (pin "1") (pinfunction "1_1") (pintype "passive"))
      (node (ref "U2") (pin "8") (pinfunction "USBDP_8") (pintype "bidirectional"))
    )
    (net (code "59") (name "VCC") (class "Default")
      (node (ref "3.3_SENSE") (pin "2") (pinfunction "VIN_2") (pintype "power_in"))
      (node (ref "5V_CHARGE_PUMP") (pin "2") (pinfunction "VIN_2") (pintype "power_in"))
      (node (ref "C14") (pin "A1") (pinfunction "1_A1") (pintype "passive"))
      (node (ref "CLOCK") (pin "1") (pinfunction "VIN_1") (pintype "bidirectional"))
      (node (ref "CLOCK_CIN") (pin "1") (pinfunction "1_1") (pintype "passive"))
      (node (ref "CN1") (pin "1") (pinfunction "2_1") (pintype "passive"))
      (node (ref "COUT") (pin "1") (pinfunction "1_1") (pintype "passive"))
      (node (ref "C_BOOST_1") (pin "2") (pinfunction "2_2") (pintype "passive"))
      (node (ref "H1") (pin "7") (pinfunction "7_7") (pintype "passive"))
      (node (ref "H3") (pin "4") (pinfunction "4_4") (pintype "passive"))
      (node (ref "IC1") (pin "6") (pinfunction "SEN_6") (pintype "input"))
      (node (ref "ISP") (pin "2") (pinfunction "VCC_2") (pintype "power_in"))
      (node (ref "J1") (pin "PWR") (pinfunction "PWR_PWR") (pintype "bidirectional"))
      (node (ref "LD0_SD") (pin "1") (pinfunction "VIN_1") (pintype "bidirectional"))
      (node (ref "L_LPF") (pin "1") (pinfunction "1_1") (pintype "passive"))
      (node (ref "MCU") (pin "4") (pinfunction "VCC_4") (pintype "power_in"))
      (node (ref "MCU") (pin "6") (pinfunction "VCC_2_6") (pintype "power_in"))
      (node (ref "Q1") (pin "2") (pinfunction "S_2") (pintype "passive"))
      (node (ref "Q2") (pin "2") (pinfunction "S_2") (pintype "passive"))
      (node (ref "RCKL1") (pin "2") (pinfunction "2_2") (pintype "passive"))
      (node (ref "RN2") (pin "1") (pinfunction "1_1") (pintype "passive"))
      (node (ref "RN2") (pin "2") (pinfunction "1_2") (pintype "passive"))
      (node (ref "RSTAT") (pin "2") (pinfunction "2_2") (pintype "passive"))
      (node (ref "R_RESET") (pin "2") (pinfunction "2_2") (pintype "passive"))
      (node (ref "SD_CIN") (pin "1") (pinfunction "1_1") (pintype "passive"))
      (node (ref "SENSE_CIN") (pin "1") (pinfunction "1_1") (pintype "passive"))
    )
    (net (code "60") (name "VDD") (class "Default")
      (node (ref "C14") (pin "B1") (pinfunction "1_B1") (pintype "passive"))
      (node (ref "C_LDO_SD") (pin "2") (pinfunction "2_2") (pintype "passive"))
      (node (ref "LD0_SD") (pin "5") (pinfunction "VOUT_5") (pintype "bidirectional"))
      (node (ref "LSHIFT") (pin "1") (pinfunction "VDD_1") (pintype "power_in"))
      (node (ref "Q3") (pin "1") (pinfunction "G_1") (pintype "passive"))
      (node (ref "Q4") (pin "1") (pinfunction "G_1") (pintype "passive"))
      (node (ref "SD") (pin "4") (pinfunction "VDD_4") (pintype "power_in"))
    )
    (net (code "61") (name "VUSB") (class "Default")
      (node (ref "C17") (pin "1") (pinfunction "1_1") (pintype "passive"))
      (node (ref "C21") (pin "A") (pinfunction "+_A") (pintype "passive"))
      (node (ref "JP5") (pin "VBUS") (pinfunction "VBUS_VBUS") (pintype "bidirectional"))
      (node (ref "Q2") (pin "3") (pinfunction "D_3") (pintype "passive"))
      (node (ref "RN1") (pin "5") (pinfunction "2_5") (pintype "passive"))
      (node (ref "RN1") (pin "6") (pinfunction "2_6") (pintype "passive"))
      (node (ref "U2") (pin "12") (pinfunction "VCC_12") (pintype "bidirectional"))
    )
    (net (code "62") (name "unconnected-(3.3_SENSE-DNC-Pad8)") (class "Default")
      (node (ref "3.3_SENSE") (pin "8") (pinfunction "DNC_8") (pintype "no_connect"))
    )
    (net (code "63") (name "unconnected-(3.3_SENSE-DNC_2-Pad1)") (class "Default")
      (node (ref "3.3_SENSE") (pin "1") (pinfunction "DNC_2_1") (pintype "no_connect"))
    )
    (net (code "64") (name "unconnected-(3.3_SENSE-DNC_3-Pad5)") (class "Default")
      (node (ref "3.3_SENSE") (pin "5") (pinfunction "DNC_3_5") (pintype "no_connect"))
    )
    (net (code "65") (name "unconnected-(3.3_SENSE-DNC_4-Pad7)") (class "Default")
      (node (ref "3.3_SENSE") (pin "7") (pinfunction "DNC_4_7") (pintype "no_connect"))
    )
    (net (code "66") (name "unconnected-(CLOCK-BYP-Pad4)") (class "Default")
      (node (ref "CLOCK") (pin "4") (pinfunction "BYP_4") (pintype "bidirectional"))
    )
    (net (code "67") (name "unconnected-(LD0_SD-BYP-Pad4)") (class "Default")
      (node (ref "LD0_SD") (pin "4") (pinfunction "BYP_4") (pintype "bidirectional"))
    )
    (net (code "68") (name "unconnected-(LSHIFTD-O-Pad10)") (class "Default")
      (node (ref "LSHIFT") (pin "10") (pinfunction "O_10") (pintype "output"))
    )
    (net (code "69") (name "unconnected-(LSHIFTE-O-Pad12)") (class "Default")
      (node (ref "LSHIFT") (pin "12") (pinfunction "O_12") (pintype "output"))
    )
    (net (code "70") (name "unconnected-(LSHIFTF-O-Pad15)") (class "Default")
      (node (ref "LSHIFT") (pin "15") (pinfunction "O_15") (pintype "output"))
    )
    (net (code "71") (name "unconnected-(MCU-EP-Pad33)") (class "Default")
      (node (ref "MCU") (pin "33") (pinfunction "EP_33") (pintype "passive"))
    )
    (net (code "72") (name "unconnected-(SD-CARD_DETECT-PadCD)") (class "Default")
      (node (ref "SD") (pin "CD") (pinfunction "CARD_DETECT_CD") (pintype "passive"))
    )
    (net (code "73") (name "unconnected-(SD-DAT1-Pad8)") (class "Default")
      (node (ref "SD") (pin "8") (pinfunction "DAT1_8") (pintype "bidirectional"))
    )
    (net (code "74") (name "unconnected-(SD-DAT2-Pad9)") (class "Default")
      (node (ref "SD") (pin "9") (pinfunction "DAT2_9") (pintype "bidirectional"))
    )
    (net (code "75") (name "unconnected-(SD-WRITE_PROTECT-PadWP)") (class "Default")
      (node (ref "SD") (pin "WP") (pinfunction "WRITE_PROTECT_WP") (pintype "passive"))
    )
    (net (code "76") (name "unconnected-(U1-*RST-Pad4)") (class "Default")
      (node (ref "U1") (pin "4") (pinfunction "*RST_4") (pintype "passive"))
    )
    (net (code "77") (name "unconnected-(U1-32KHZ-Pad1)") (class "Default")
      (node (ref "U1") (pin "1") (pinfunction "32KHZ_1") (pintype "passive"))
    )
    (net (code "78") (name "unconnected-(U2-CBUS0-Pad15)") (class "Default")
      (node (ref "U2") (pin "15") (pinfunction "CBUS0_15") (pintype "bidirectional"))
    )
    (net (code "79") (name "unconnected-(U2-CBUS3-Pad16)") (class "Default")
      (node (ref "U2") (pin "16") (pinfunction "CBUS3_16") (pintype "bidirectional"))
    )
    (net (code "80") (name "unconnected-(U2-DCD#-Pad5)") (class "Default")
      (node (ref "U2") (pin "5") (pinfunction "DCD#_5") (pintype "bidirectional"))
    )
    (net (code "81") (name "unconnected-(U2-DSR#-Pad4)") (class "Default")
      (node (ref "U2") (pin "4") (pinfunction "DSR#_4") (pintype "bidirectional"))
    )
    (net (code "82") (name "unconnected-(U2-RI#-Pad2)") (class "Default")
      (node (ref "U2") (pin "2") (pinfunction "RI#_2") (pintype "bidirectional"))
    )
    (net (code "83") (name "unconnected-(U2-RTS#-Pad19)") (class "Default")
      (node (ref "U2") (pin "19") (pinfunction "RTS#_19") (pintype "bidirectional"))
    )
  )
)
